# vco-test-both-sides-2.net
KiCad netlist of a schematic drawn in EAGLE
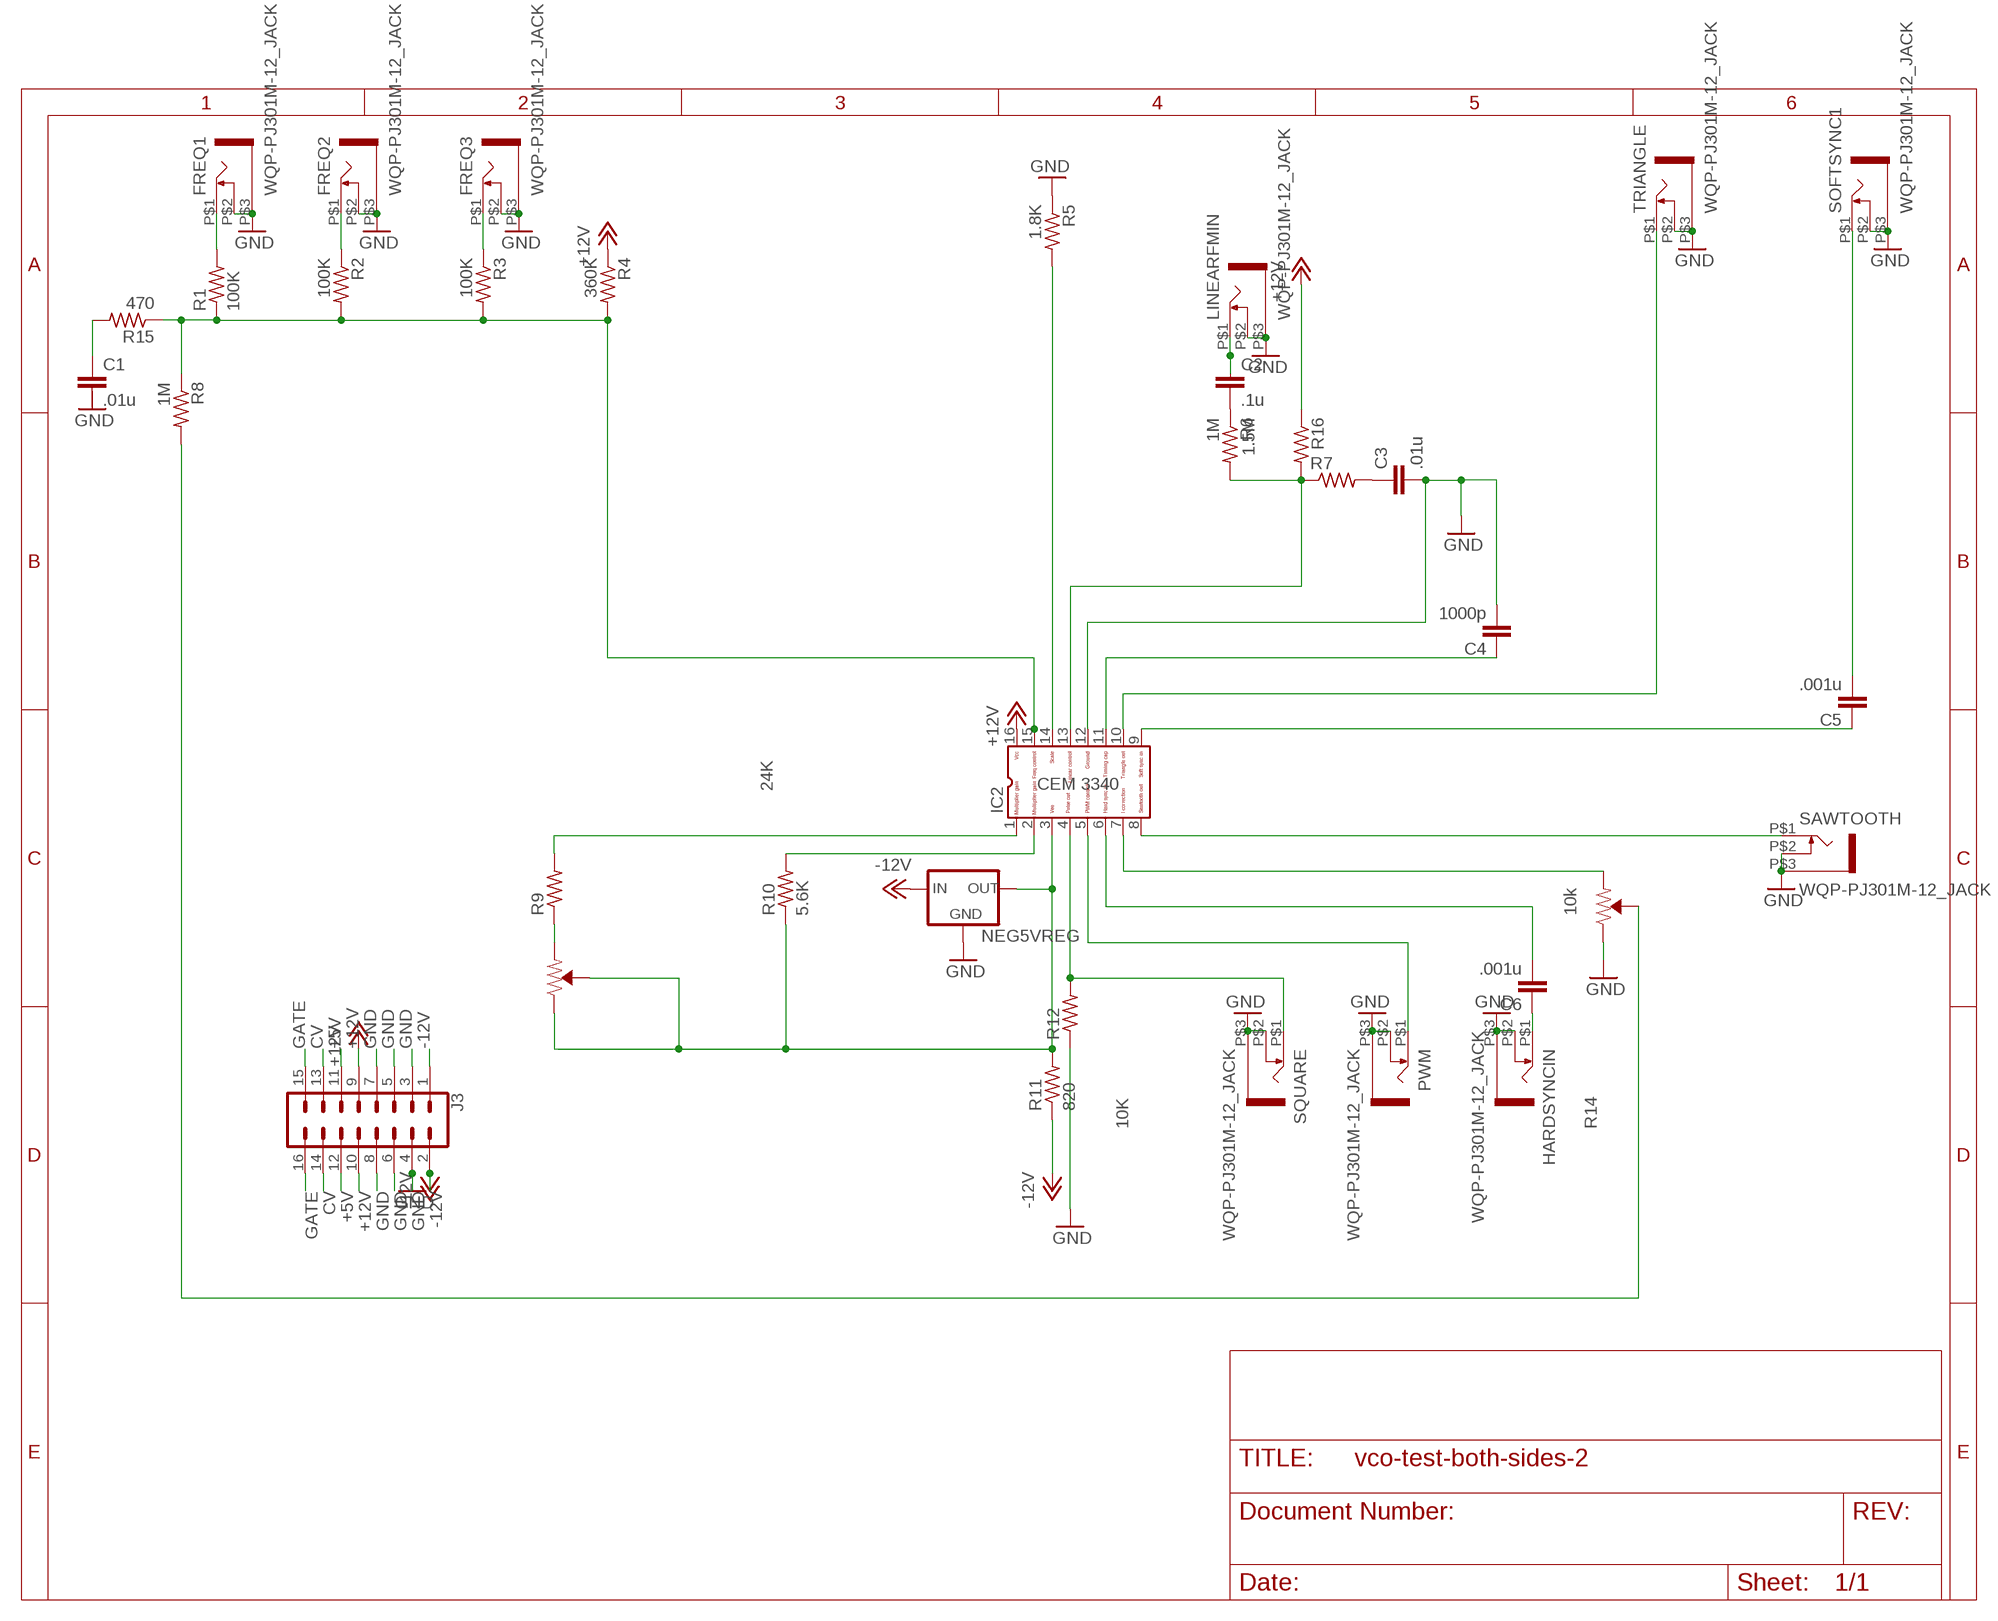
[diagram p0: schematic, sheet 1]

(export (version "E")
  (design (tool "Eeschema 10.0.6"))
  (components
    (comp (ref "C1")
      (value ".01u")
      (footprint "eagle-import:C050-025X075")
      (libsource (lib "eagle-import") (part "C-EU050-025X075"))
    )
    (comp (ref "C2")
      (value ".1u")
      (footprint "eagle-import:C050-025X075")
      (libsource (lib "eagle-import") (part "C-EU050-025X075"))
    )
    (comp (ref "C3")
      (value ".01u")
      (footprint "eagle-import:C050-025X075")
      (libsource (lib "eagle-import") (part "C-EU050-025X075"))
    )
    (comp (ref "C4")
      (value "1000p")
      (footprint "eagle-import:C050-025X075")
      (libsource (lib "eagle-import") (part "C-EU050-025X075"))
    )
    (comp (ref "C5")
      (value ".001u")
      (footprint "eagle-import:C050-025X075")
      (libsource (lib "eagle-import") (part "C-EU050-025X075"))
    )
    (comp (ref "C6")
      (value ".001u")
      (footprint "eagle-import:C050-025X075")
      (libsource (lib "eagle-import") (part "C-EU050-025X075"))
    )
    (comp (ref "FREQ1")
      (value "WQP-PJ301M-12_JACK")
      (footprint "eagle-import:WQP-PJ301M-12_JACK")
      (libsource (lib "eagle-import") (part "WQP-PJ301M-12_JACK"))
    )
    (comp (ref "FREQ2")
      (value "WQP-PJ301M-12_JACK")
      (footprint "eagle-import:WQP-PJ301M-12_JACK")
      (fields (field (name "SPICEPREFIX") "U"))
      (libsource (lib "eagle-import") (part "WQP-PJ301M-12_JACK"))
    )
    (comp (ref "FREQ3")
      (value "WQP-PJ301M-12_JACK")
      (footprint "eagle-import:WQP-PJ301M-12_JACK")
      (libsource (lib "eagle-import") (part "WQP-PJ301M-12_JACK"))
    )
    (comp (ref "HARDSYNCIN")
      (value "WQP-PJ301M-12_JACK")
      (footprint "eagle-import:WQP-PJ301M-12_JACK")
      (libsource (lib "eagle-import") (part "WQP-PJ301M-12_JACK"))
    )
    (comp (ref "IC2")
      (value "CEM3340")
      (footprint "eagle-import:DIL16")
      (libsource (lib "eagle-import") (part "CEM3340"))
    )
    (comp (ref "J3")
      (value "CONN_08X2_SHROUD")
      (footprint "eagle-import:2X8-SHROUDED_LOCK")
      (libsource (lib "eagle-import") (part "CONN_08X2_SHROUD"))
    )
    (comp (ref "LINEARFMIN")
      (value "WQP-PJ301M-12_JACK")
      (footprint "eagle-import:WQP-PJ301M-12_JACK")
      (libsource (lib "eagle-import") (part "WQP-PJ301M-12_JACK"))
    )
    (comp (ref "NEG5VREG")
      (value "V_REG_78XXTO-92_UNTESTED")
      (footprint "eagle-import:TO-92")
      (libsource (lib "eagle-import") (part "V_REG_78XXTO-92_UNTESTED"))
    )
    (comp (ref "PWM")
      (value "WQP-PJ301M-12_JACK")
      (footprint "eagle-import:WQP-PJ301M-12_JACK")
      (libsource (lib "eagle-import") (part "WQP-PJ301M-12_JACK"))
    )
    (comp (ref "R1")
      (value "100K")
      (footprint "eagle-import:0207_10")
      (libsource (lib "eagle-import") (part "R-US_0207/10"))
    )
    (comp (ref "R2")
      (value "100K")
      (footprint "eagle-import:0207_10")
      (libsource (lib "eagle-import") (part "R-US_0207/10"))
    )
    (comp (ref "R3")
      (value "100K")
      (footprint "eagle-import:0207_10")
      (libsource (lib "eagle-import") (part "R-US_0207/10"))
    )
    (comp (ref "R4")
      (value "360K")
      (footprint "eagle-import:0207_10")
      (libsource (lib "eagle-import") (part "R-US_0207/10"))
    )
    (comp (ref "R5")
      (value "1.8K")
      (footprint "eagle-import:0207_10")
      (libsource (lib "eagle-import") (part "R-US_0207/10"))
    )
    (comp (ref "R6")
      (value "1M")
      (footprint "eagle-import:0207_10")
      (libsource (lib "eagle-import") (part "R-US_0207/10"))
    )
    (comp (ref "R7")
      (value "R-US_0207/10")
      (footprint "eagle-import:0207_10")
      (libsource (lib "eagle-import") (part "R-US_0207/10"))
    )
    (comp (ref "R8")
      (value "1M")
      (footprint "eagle-import:0207_10")
      (libsource (lib "eagle-import") (part "R-US_0207/10"))
    )
    (comp (ref "R9")
      (value "24K")
      (footprint "eagle-import:0207_10")
      (libsource (lib "eagle-import") (part "R-US_0207/10"))
    )
    (comp (ref "R10")
      (value "5.6K")
      (footprint "eagle-import:0207_10")
      (libsource (lib "eagle-import") (part "R-US_0207/10"))
    )
    (comp (ref "R11")
      (value "820")
      (footprint "eagle-import:0207_10")
      (libsource (lib "eagle-import") (part "R-US_0207/10"))
    )
    (comp (ref "R12")
      (value "10K")
      (footprint "eagle-import:0207_10")
      (libsource (lib "eagle-import") (part "R-US_0207/10"))
    )
    (comp (ref "R13")
      (value "10k")
      (footprint "eagle-import:TRIMPOT-PTH-3386U")
      (libsource (lib "eagle-import") (part "TRIMPOT-PTH-10MM-KNOB-1/2W-10%"))
    )
    (comp (ref "R14")
      (value "10k")
      (footprint "eagle-import:TRIMPOT-PTH-3386U")
      (libsource (lib "eagle-import") (part "TRIMPOT-PTH-10MM-KNOB-1/2W-10%"))
    )
    (comp (ref "R15")
      (value "470")
      (footprint "eagle-import:0207_10")
      (libsource (lib "eagle-import") (part "R-US_0207/10"))
    )
    (comp (ref "R16")
      (value "1.5M")
      (footprint "eagle-import:0207_10")
      (libsource (lib "eagle-import") (part "R-US_0207/10"))
    )
    (comp (ref "SAWTOOTH")
      (value "WQP-PJ301M-12_JACK")
      (footprint "eagle-import:WQP-PJ301M-12_JACK")
      (libsource (lib "eagle-import") (part "WQP-PJ301M-12_JACK"))
    )
    (comp (ref "SOFTSYNC1")
      (value "WQP-PJ301M-12_JACK")
      (footprint "eagle-import:WQP-PJ301M-12_JACK")
      (libsource (lib "eagle-import") (part "WQP-PJ301M-12_JACK"))
    )
    (comp (ref "SQUARE")
      (value "WQP-PJ301M-12_JACK")
      (footprint "eagle-import:WQP-PJ301M-12_JACK")
      (libsource (lib "eagle-import") (part "WQP-PJ301M-12_JACK"))
    )
    (comp (ref "TRIANGLE")
      (value "WQP-PJ301M-12_JACK")
      (footprint "eagle-import:WQP-PJ301M-12_JACK")
      (libsource (lib "eagle-import") (part "WQP-PJ301M-12_JACK"))
    )
  )
  (nets
    (net (code "1") (name "+12V") (class "Default")
      (node (ref "IC2") (pin "16") (pinfunction "16_16") (pintype "power_in"))
      (node (ref "J3") (pin "10") (pinfunction "10_10") (pintype "passive"))
      (node (ref "J3") (pin "9") (pinfunction "9_9") (pintype "passive"))
      (node (ref "R16") (pin "1") (pinfunction "1_1") (pintype "passive"))
      (node (ref "R4") (pin "1") (pinfunction "1_1") (pintype "passive"))
    )
    (net (code "2") (name "-12V") (class "Default")
      (node (ref "J3") (pin "1") (pinfunction "1_1") (pintype "passive"))
      (node (ref "J3") (pin "2") (pinfunction "2_2") (pintype "passive"))
      (node (ref "NEG5VREG") (pin "3") (pinfunction "IN_3") (pintype "input"))
      (node (ref "R11") (pin "1") (pinfunction "1_1") (pintype "passive"))
    )
    (net (code "3") (name "/+5V") (class "Default")
      (node (ref "J3") (pin "11") (pinfunction "11_11") (pintype "passive"))
      (node (ref "J3") (pin "12") (pinfunction "12_12") (pintype "passive"))
    )
    (net (code "4") (name "/CV") (class "Default")
      (node (ref "J3") (pin "13") (pinfunction "13_13") (pintype "passive"))
      (node (ref "J3") (pin "14") (pinfunction "14_14") (pintype "passive"))
    )
    (net (code "5") (name "/GATE") (class "Default")
      (node (ref "J3") (pin "15") (pinfunction "15_15") (pintype "passive"))
      (node (ref "J3") (pin "16") (pinfunction "16_16") (pintype "passive"))
    )
    (net (code "6") (name "GND") (class "Default")
      (node (ref "C3") (pin "2") (pinfunction "2_2") (pintype "passive"))
      (node (ref "C4") (pin "2") (pinfunction "2_2") (pintype "passive"))
      (node (ref "FREQ1") (pin "P$2") (pinfunction "3_P$2") (pintype "passive"))
      (node (ref "FREQ1") (pin "P$3") (pinfunction "1_P$3") (pintype "passive"))
      (node (ref "FREQ2") (pin "P$2") (pinfunction "3_P$2") (pintype "passive"))
      (node (ref "FREQ2") (pin "P$3") (pinfunction "1_P$3") (pintype "passive"))
      (node (ref "FREQ3") (pin "P$2") (pinfunction "3_P$2") (pintype "passive"))
      (node (ref "FREQ3") (pin "P$3") (pinfunction "1_P$3") (pintype "passive"))
      (node (ref "HARDSYNCIN") (pin "P$2") (pinfunction "3_P$2") (pintype "passive"))
      (node (ref "HARDSYNCIN") (pin "P$3") (pinfunction "1_P$3") (pintype "passive"))
      (node (ref "IC2") (pin "12") (pinfunction "12_12") (pintype "power_in"))
      (node (ref "J3") (pin "3") (pinfunction "3_3") (pintype "passive"))
      (node (ref "J3") (pin "4") (pinfunction "4_4") (pintype "passive"))
      (node (ref "J3") (pin "5") (pinfunction "5_5") (pintype "passive"))
      (node (ref "J3") (pin "6") (pinfunction "6_6") (pintype "passive"))
      (node (ref "J3") (pin "7") (pinfunction "7_7") (pintype "passive"))
      (node (ref "J3") (pin "8") (pinfunction "8_8") (pintype "passive"))
      (node (ref "LINEARFMIN") (pin "P$2") (pinfunction "3_P$2") (pintype "passive"))
      (node (ref "LINEARFMIN") (pin "P$3") (pinfunction "1_P$3") (pintype "passive"))
      (node (ref "NEG5VREG") (pin "2") (pinfunction "GND_2") (pintype "input"))
      (node (ref "PWM") (pin "P$2") (pinfunction "3_P$2") (pintype "passive"))
      (node (ref "PWM") (pin "P$3") (pinfunction "1_P$3") (pintype "passive"))
      (node (ref "R12") (pin "1") (pinfunction "1_1") (pintype "passive"))
      (node (ref "R14") (pin "3") (pinfunction "CW_3") (pintype "passive"))
      (node (ref "R5") (pin "1") (pinfunction "1_1") (pintype "passive"))
      (node (ref "SAWTOOTH") (pin "P$2") (pinfunction "3_P$2") (pintype "passive"))
      (node (ref "SAWTOOTH") (pin "P$3") (pinfunction "1_P$3") (pintype "passive"))
      (node (ref "SOFTSYNC1") (pin "P$2") (pinfunction "3_P$2") (pintype "passive"))
      (node (ref "SOFTSYNC1") (pin "P$3") (pinfunction "1_P$3") (pintype "passive"))
      (node (ref "SQUARE") (pin "P$2") (pinfunction "3_P$2") (pintype "passive"))
      (node (ref "SQUARE") (pin "P$3") (pinfunction "1_P$3") (pintype "passive"))
      (node (ref "TRIANGLE") (pin "P$2") (pinfunction "3_P$2") (pintype "passive"))
      (node (ref "TRIANGLE") (pin "P$3") (pinfunction "1_P$3") (pintype "passive"))
    )
    (net (code "7") (name "Net-(C1-Pad1)") (class "Default")
      (node (ref "C1") (pin "1") (pinfunction "1_1") (pintype "passive"))
      (node (ref "R15") (pin "2") (pinfunction "2_2") (pintype "passive"))
    )
    (net (code "8") (name "Net-(C2-Pad2)") (class "Default")
      (node (ref "C2") (pin "2") (pinfunction "2_2") (pintype "passive"))
      (node (ref "R6") (pin "1") (pinfunction "1_1") (pintype "passive"))
    )
    (net (code "9") (name "Net-(C3-Pad1)") (class "Default")
      (node (ref "C3") (pin "1") (pinfunction "1_1") (pintype "passive"))
      (node (ref "R7") (pin "2") (pinfunction "2_2") (pintype "passive"))
    )
    (net (code "10") (name "Net-(C4-Pad1)") (class "Default")
      (node (ref "C4") (pin "1") (pinfunction "1_1") (pintype "passive"))
      (node (ref "IC2") (pin "11") (pinfunction "11_11") (pintype "bidirectional"))
    )
    (net (code "11") (name "Net-(C5-Pad1)") (class "Default")
      (node (ref "C5") (pin "1") (pinfunction "1_1") (pintype "passive"))
      (node (ref "IC2") (pin "9") (pinfunction "9_9") (pintype "input"))
    )
    (net (code "12") (name "Net-(C6-Pad2)") (class "Default")
      (node (ref "C6") (pin "2") (pinfunction "2_2") (pintype "passive"))
      (node (ref "IC2") (pin "6") (pinfunction "6_6") (pintype "input"))
    )
    (net (code "13") (name "Net-(FREQ1-2)") (class "Default")
      (node (ref "FREQ1") (pin "P$1") (pinfunction "2_P$1") (pintype "passive"))
      (node (ref "R1") (pin "2") (pinfunction "2_2") (pintype "passive"))
    )
    (net (code "14") (name "Net-(FREQ2-2)") (class "Default")
      (node (ref "FREQ2") (pin "P$1") (pinfunction "2_P$1") (pintype "passive"))
      (node (ref "R2") (pin "1") (pinfunction "1_1") (pintype "passive"))
    )
    (net (code "15") (name "Net-(FREQ3-2)") (class "Default")
      (node (ref "FREQ3") (pin "P$1") (pinfunction "2_P$1") (pintype "passive"))
      (node (ref "R3") (pin "1") (pinfunction "1_1") (pintype "passive"))
    )
    (net (code "16") (name "Net-(HARDSYNCIN-2)") (class "Default")
      (node (ref "C6") (pin "1") (pinfunction "1_1") (pintype "passive"))
      (node (ref "HARDSYNCIN") (pin "P$1") (pinfunction "2_P$1") (pintype "passive"))
    )
    (net (code "17") (name "Net-(IC2-Pad1)") (class "Default")
      (node (ref "IC2") (pin "1") (pinfunction "1_1") (pintype "bidirectional"))
      (node (ref "R9") (pin "2") (pinfunction "2_2") (pintype "passive"))
    )
    (net (code "18") (name "Net-(IC2-Pad2)") (class "Default")
      (node (ref "IC2") (pin "2") (pinfunction "2_2") (pintype "bidirectional"))
      (node (ref "R10") (pin "2") (pinfunction "2_2") (pintype "passive"))
    )
    (net (code "19") (name "Net-(IC2-Pad13)") (class "Default")
      (node (ref "IC2") (pin "13") (pinfunction "13_13") (pintype "input"))
      (node (ref "R16") (pin "2") (pinfunction "2_2") (pintype "passive"))
      (node (ref "R6") (pin "2") (pinfunction "2_2") (pintype "passive"))
      (node (ref "R7") (pin "1") (pinfunction "1_1") (pintype "passive"))
    )
    (net (code "20") (name "Net-(IC2-Pad14)") (class "Default")
      (node (ref "IC2") (pin "14") (pinfunction "14_14") (pintype "input"))
      (node (ref "R5") (pin "2") (pinfunction "2_2") (pintype "passive"))
    )
    (net (code "21") (name "Net-(IC2-Pad15)") (class "Default")
      (node (ref "IC2") (pin "15") (pinfunction "15_15") (pintype "input"))
      (node (ref "R1") (pin "1") (pinfunction "1_1") (pintype "passive"))
      (node (ref "R15") (pin "1") (pinfunction "1_1") (pintype "passive"))
      (node (ref "R2") (pin "2") (pinfunction "2_2") (pintype "passive"))
      (node (ref "R3") (pin "2") (pinfunction "2_2") (pintype "passive"))
      (node (ref "R4") (pin "2") (pinfunction "2_2") (pintype "passive"))
      (node (ref "R8") (pin "1") (pinfunction "1_1") (pintype "passive"))
    )
    (net (code "22") (name "Net-(LINEARFMIN-2)") (class "Default")
      (node (ref "C2") (pin "1") (pinfunction "1_1") (pintype "passive"))
      (node (ref "LINEARFMIN") (pin "P$1") (pinfunction "2_P$1") (pintype "passive"))
    )
    (net (code "23") (name "Net-(NEG5VREG-OUT)") (class "Default")
      (node (ref "IC2") (pin "3") (pinfunction "3_3") (pintype "power_in"))
      (node (ref "NEG5VREG") (pin "1") (pinfunction "OUT_1") (pintype "passive"))
      (node (ref "R10") (pin "1") (pinfunction "1_1") (pintype "passive"))
      (node (ref "R11") (pin "2") (pinfunction "2_2") (pintype "passive"))
      (node (ref "R13") (pin "2") (pinfunction "WIPER_2") (pintype "passive"))
      (node (ref "R13") (pin "3") (pinfunction "CW_3") (pintype "passive"))
    )
    (net (code "24") (name "Net-(PWM-2)") (class "Default")
      (node (ref "IC2") (pin "5") (pinfunction "5_5") (pintype "input"))
      (node (ref "PWM") (pin "P$1") (pinfunction "2_P$1") (pintype "passive"))
    )
    (net (code "25") (name "Net-(R13-CCW)") (class "Default")
      (node (ref "R13") (pin "1") (pinfunction "CCW_1") (pintype "passive"))
      (node (ref "R9") (pin "1") (pinfunction "1_1") (pintype "passive"))
    )
    (net (code "26") (name "Net-(R14-CCW)") (class "Default")
      (node (ref "IC2") (pin "7") (pinfunction "7_7") (pintype "bidirectional"))
      (node (ref "R14") (pin "1") (pinfunction "CCW_1") (pintype "passive"))
    )
    (net (code "27") (name "Net-(R14-WIPER)") (class "Default")
      (node (ref "R14") (pin "2") (pinfunction "WIPER_2") (pintype "passive"))
      (node (ref "R8") (pin "2") (pinfunction "2_2") (pintype "passive"))
    )
    (net (code "28") (name "Net-(SAWTOOTH-2)") (class "Default")
      (node (ref "IC2") (pin "8") (pinfunction "8_8") (pintype "output"))
      (node (ref "SAWTOOTH") (pin "P$1") (pinfunction "2_P$1") (pintype "passive"))
    )
    (net (code "29") (name "Net-(SOFTSYNC1-2)") (class "Default")
      (node (ref "C5") (pin "2") (pinfunction "2_2") (pintype "passive"))
      (node (ref "SOFTSYNC1") (pin "P$1") (pinfunction "2_P$1") (pintype "passive"))
    )
    (net (code "30") (name "Net-(SQUARE-2)") (class "Default")
      (node (ref "IC2") (pin "4") (pinfunction "4_4") (pintype "output"))
      (node (ref "R12") (pin "2") (pinfunction "2_2") (pintype "passive"))
      (node (ref "SQUARE") (pin "P$1") (pinfunction "2_P$1") (pintype "passive"))
    )
    (net (code "31") (name "Net-(TRIANGLE-2)") (class "Default")
      (node (ref "IC2") (pin "10") (pinfunction "10_10") (pintype "output"))
      (node (ref "TRIANGLE") (pin "P$1") (pinfunction "2_P$1") (pintype "passive"))
    )
    (net (code "32") (name "unconnected-(C1-Pad2)") (class "Default")
      (node (ref "C1") (pin "2") (pinfunction "2_2") (pintype "passive"))
    )
  )
)
